# Sheet1.net
KiCad netlist of a schematic drawn in Altium Designer
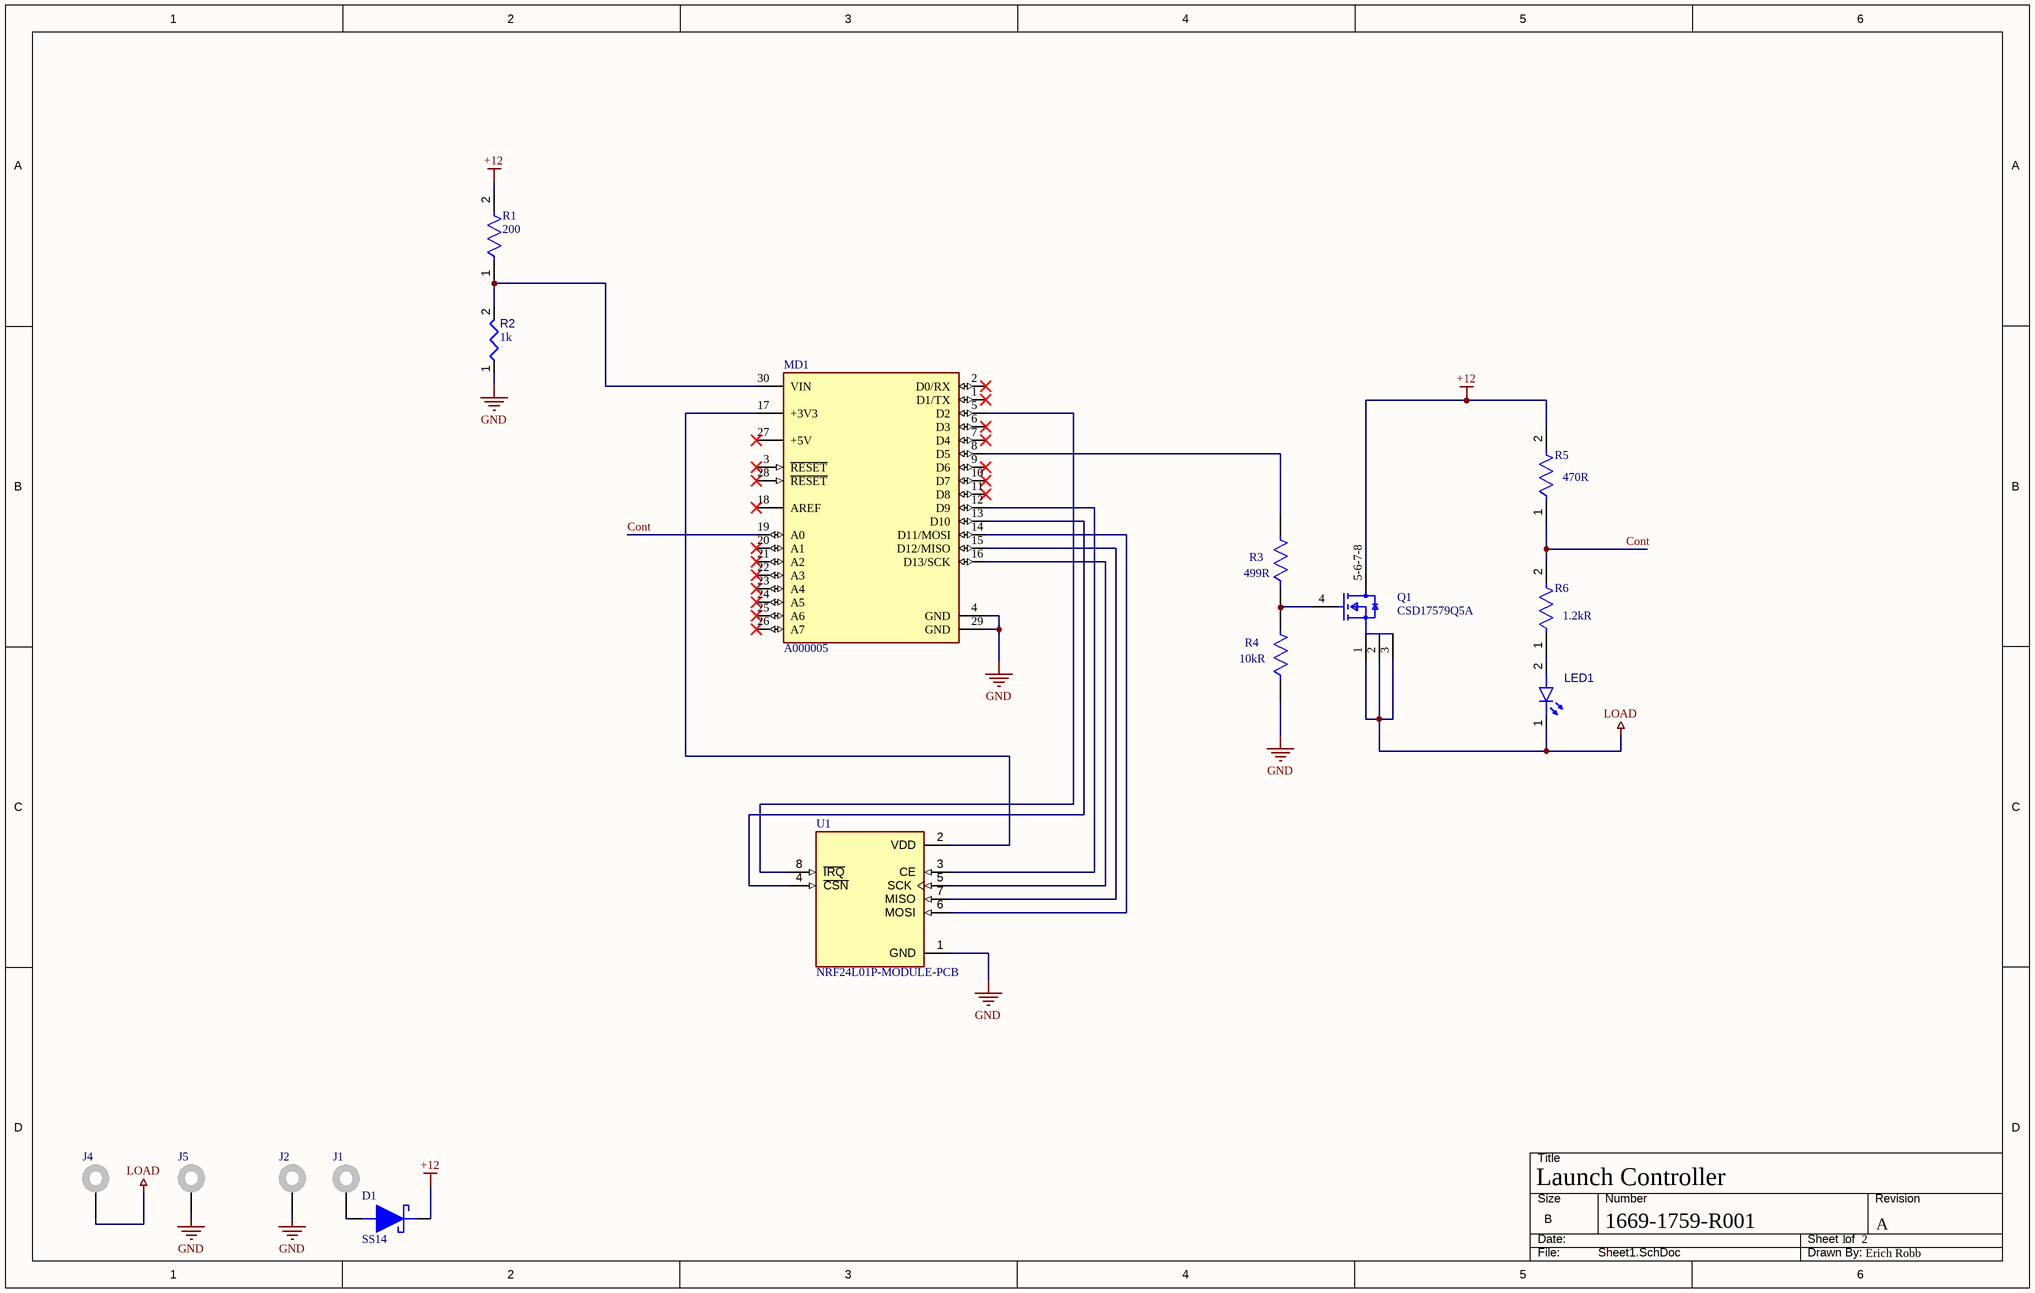
[diagram p0: Sheet1.SchDoc]

(export (version "E")
  (design (tool "Eeschema 10.0.6"))
  (components
    (comp (ref "D1")
      (value "SS14")
      (footprint "DIOM5227X270N")
      (description "Diode Schottky 40 V 1A Surface Mount DO-214AC (SMA)")
      (fields (field (name "MF") "ON Semiconductor"))
      (libsource (lib "Erich Robb") (part "SS14"))
    )
    (comp (ref "J1")
      (value "575-8")
      (footprint "KSTN-575-8")
      (description "Non-Insulated Jack, Through Hole, RoHS, Bulk")
      (fields (field (name "MANUFACTURER") "Keystone"))
      (libsource (lib "Altium Content Vault") (part "KSTN-575-8"))
    )
    (comp (ref "J2")
      (value "575-8")
      (footprint "KSTN-575-8")
      (description "Non-Insulated Jack, Through Hole, RoHS, Bulk")
      (fields (field (name "MANUFACTURER") "Keystone"))
      (libsource (lib "Altium Content Vault") (part "KSTN-575-8"))
    )
    (comp (ref "J4")
      (value "575-8")
      (footprint "KSTN-575-8")
      (description "Non-Insulated Jack, Through Hole, RoHS, Bulk")
      (fields (field (name "MANUFACTURER") "Keystone"))
      (libsource (lib "Altium Content Vault") (part "KSTN-575-8"))
    )
    (comp (ref "J5")
      (value "575-8")
      (footprint "KSTN-575-8")
      (description "Non-Insulated Jack, Through Hole, RoHS, Bulk")
      (fields (field (name "MANUFACTURER") "Keystone"))
      (libsource (lib "Altium Content Vault") (part "KSTN-575-8"))
    )
    (comp (ref "LED1")
      (value "QBLP595-IB")
      (footprint "QTB-QBLP595_V")
      (description "Chip LED 0402, Blue, 0.02 A, 3.1 to 3.7 V, -40 to 80 degC, 2-Pin SMD, RoHS, Tape and Reel")
      (libsource (lib "Erich Robb") (part "LED-KA-2"))
    )
    (comp (ref "MD1")
      (value "A000005")
      (footprint "FP-A000005-MFG")
      (description "ARDUINO NANO ATMEGA328 EVAL BRD")
      (libsource (lib "Altium Content Vault") (part "d190c066e99afd1c6882cf92e11b2cc"))
    )
    (comp (ref "Q1")
      (value "CSD17579Q5A")
      (footprint "FP-DQJ0008A-MFG")
      (description "30V, N ch NexFET MOSFET, single SON5x6, 13.3mOhm 8-VSONP")
      (fields (field (name "MF") "Texas Instruments"))
      (libsource (lib "Erich Robb") (part "95ca5d46c4c8fe7d84c4fb5e2abfe3c"))
    )
    (comp (ref "R1")
      (value "200")
      (footprint "FP-RC3216-IPC_A")
      (fields
        (field (name "POWER") "250mW")
        (field (name "TOLERANCE") "1%")
        (field (name "Comment") "RC3216F201CS")
      )
      (libsource (lib "Erich Robb") (part "1029c3af85768c4190bb7ad29bc67b5"))
    )
    (comp (ref "R2")
      (value "1k")
      (footprint "FP-MCA1206-IPC_A")
      (description "Fixed Resistor, Thin Film, 0.25W, 1000ohm, 200V, 1% +/-Tol, 50ppm/Cel, Surface Mount, 1206")
      (fields (field (name "POWER") "250mW") (field (name "TOLERANCE") "1%"))
      (libsource (lib "Erich Robb") (part "RES-2"))
    )
    (comp (ref "R3")
      (value "499R")
      (footprint "FP-RT1206-MFG")
      (description "RES SMD 499 OHM 1% 1/4W 1206")
      (fields
        (field (name "MANUFACTURER PART NUMBER") "RT1206FRE07499RL")
        (field (name "TOLERANCE") "0.0002")
      )
      (libsource (lib "") (part "1029c3af85768c4190bb7ad29bc67b5_1"))
    )
    (comp (ref "R4")
      (value "CRCW120610K0FKEA")
      (footprint "FP-CRCW1206-e3-IPC_C")
      (description "RES Thick Film, 10kΩ, 1%, 0.25W, 100ppm/°C, 1206")
      (fields (field (name "TOLERANCE") "1%") (field (name "RESISTANCE") "10kR"))
      (libsource (lib "") (part "1029c3af85768c4190bb7ad29bc67b5_1"))
    )
    (comp (ref "R5")
      (value "CRCW1206470RJNEA")
      (footprint "FP-CRCW1206-e3-IPC_A")
      (description "RES Thick Film, 470Ω, 5%, 0.25W, 200ppm/°C, 1206")
      (fields (field (name "TOLERANCE") "5%") (field (name "RESISTANCE") "470R"))
      (libsource (lib "Altium Content Vault") (part "1029c3af85768c4190bb7ad29bc67b5"))
    )
    (comp (ref "R6")
      (value "RC3216J122CS")
      (footprint "FP-RC3216-IPC_A")
      (description "Res Thick Film 1206 1.2kΩ 5% 0.25W ±100ppm/°C Molded SMD T/R")
      (fields (field (name "TOLERANCE") "5%") (field (name "RESISTANCE") "1.2kR"))
      (libsource (lib "Altium Content Vault") (part "1029c3af85768c4190bb7ad29bc67b5"))
    )
    (comp (ref "U1")
      (value "NRF24L01P-MODULE-PCB")
      (footprint "XCVR_NRF24L01P-MODULE-PCB")
      (description "- Transceiver For Use With nRF24L01+")
      (fields (field (name "MF") "Nordic Semiconductor"))
      (libsource (lib "Erich Robb") (part "NRF24L01P-MODULE-PCB"))
    )
  )
  (nets
    (net (code "1") (name "+12") (class "Default")
      (node (ref "D1") (pin "1") (pinfunction "K_1") (pintype "passive"))
      (node (ref "Q1") (pin "5-6-7-8") (pinfunction "D_5-6-7-8") (pintype "passive"))
      (node (ref "R1") (pin "2") (pinfunction "2_2") (pintype "passive"))
      (node (ref "R5") (pin "2") (pinfunction "2_2") (pintype "passive"))
    )
    (net (code "2") (name "/Cont") (class "Default")
      (node (ref "MD1") (pin "19") (pinfunction "A0_19") (pintype "bidirectional"))
      (node (ref "R5") (pin "1") (pinfunction "1_1") (pintype "passive"))
      (node (ref "R6") (pin "2") (pinfunction "2_2") (pintype "passive"))
    )
    (net (code "3") (name "GND") (class "Default")
      (node (ref "J2") (pin "1") (pinfunction "1_1") (pintype "passive"))
      (node (ref "J5") (pin "1") (pinfunction "1_1") (pintype "passive"))
      (node (ref "MD1") (pin "29") (pinfunction "GND_29") (pintype "power_in"))
      (node (ref "MD1") (pin "4") (pinfunction "GND_4") (pintype "power_in"))
      (node (ref "R2") (pin "1") (pinfunction "1_1") (pintype "passive"))
      (node (ref "R4") (pin "1") (pinfunction "1_1") (pintype "passive"))
      (node (ref "U1") (pin "1") (pinfunction "GND_1") (pintype "power_in"))
    )
    (net (code "4") (name "LOAD") (class "Default")
      (node (ref "J4") (pin "1") (pinfunction "1_1") (pintype "passive"))
      (node (ref "LED1") (pin "1") (pinfunction "K_1") (pintype "passive"))
      (node (ref "Q1") (pin "1") (pinfunction "S_1") (pintype "passive"))
      (node (ref "Q1") (pin "2") (pinfunction "S_2") (pintype "passive"))
      (node (ref "Q1") (pin "3") (pinfunction "S_3") (pintype "passive"))
    )
    (net (code "5") (name "Net-(D1-A)") (class "Default")
      (node (ref "D1") (pin "2") (pinfunction "A_2") (pintype "passive"))
      (node (ref "J1") (pin "1") (pinfunction "1_1") (pintype "passive"))
    )
    (net (code "6") (name "Net-(LED1-A)") (class "Default")
      (node (ref "LED1") (pin "2") (pinfunction "A_2") (pintype "passive"))
      (node (ref "R6") (pin "1") (pinfunction "1_1") (pintype "passive"))
    )
    (net (code "7") (name "Net-(MD1-+3V3)") (class "Default")
      (node (ref "MD1") (pin "17") (pinfunction "+3V3_17") (pintype "power_in"))
      (node (ref "U1") (pin "2") (pinfunction "VDD_2") (pintype "power_in"))
    )
    (net (code "8") (name "Net-(MD1-D2)") (class "Default")
      (node (ref "MD1") (pin "5") (pinfunction "D2_5") (pintype "bidirectional"))
      (node (ref "U1") (pin "8") (pinfunction "~{IRQ}_8") (pintype "input"))
    )
    (net (code "9") (name "Net-(MD1-D5)") (class "Default")
      (node (ref "MD1") (pin "8") (pinfunction "D5_8") (pintype "bidirectional"))
      (node (ref "R3") (pin "2") (pinfunction "2_2") (pintype "passive"))
    )
    (net (code "10") (name "Net-(MD1-D9)") (class "Default")
      (node (ref "MD1") (pin "12") (pinfunction "D9_12") (pintype "bidirectional"))
      (node (ref "U1") (pin "3") (pinfunction "CE_3") (pintype "input"))
    )
    (net (code "11") (name "Net-(MD1-D10)") (class "Default")
      (node (ref "MD1") (pin "13") (pinfunction "D10_13") (pintype "bidirectional"))
      (node (ref "U1") (pin "4") (pinfunction "~{CSN}_4") (pintype "input"))
    )
    (net (code "12") (name "Net-(MD1-D11{slash}MOSI)") (class "Default")
      (node (ref "MD1") (pin "14") (pinfunction "D11/MOSI_14") (pintype "bidirectional"))
      (node (ref "U1") (pin "6") (pinfunction "MOSI_6") (pintype "input"))
    )
    (net (code "13") (name "Net-(MD1-D12{slash}MISO)") (class "Default")
      (node (ref "MD1") (pin "15") (pinfunction "D12/MISO_15") (pintype "bidirectional"))
      (node (ref "U1") (pin "7") (pinfunction "MISO_7") (pintype "input"))
    )
    (net (code "14") (name "Net-(MD1-D13{slash}SCK)") (class "Default")
      (node (ref "MD1") (pin "16") (pinfunction "D13/SCK_16") (pintype "bidirectional"))
      (node (ref "U1") (pin "5") (pinfunction "SCK_5") (pintype "input"))
    )
    (net (code "15") (name "Net-(MD1-VIN)") (class "Default")
      (node (ref "MD1") (pin "30") (pinfunction "VIN_30") (pintype "power_in"))
      (node (ref "R1") (pin "1") (pinfunction "1_1") (pintype "passive"))
      (node (ref "R2") (pin "2") (pinfunction "2_2") (pintype "passive"))
    )
    (net (code "16") (name "Net-(Q1-G)") (class "Default")
      (node (ref "Q1") (pin "4") (pinfunction "G_4") (pintype "passive"))
      (node (ref "R3") (pin "1") (pinfunction "1_1") (pintype "passive"))
      (node (ref "R4") (pin "2") (pinfunction "2_2") (pintype "passive"))
    )
    (net (code "17") (name "unconnected-(MD1-+5V-Pad27)") (class "Default")
      (node (ref "MD1") (pin "27") (pinfunction "+5V_27") (pintype "power_in+no_connect"))
    )
    (net (code "18") (name "unconnected-(MD1-A1-Pad20)") (class "Default")
      (node (ref "MD1") (pin "20") (pinfunction "A1_20") (pintype "bidirectional+no_connect"))
    )
    (net (code "19") (name "unconnected-(MD1-A2-Pad21)") (class "Default")
      (node (ref "MD1") (pin "21") (pinfunction "A2_21") (pintype "bidirectional+no_connect"))
    )
    (net (code "20") (name "unconnected-(MD1-A3-Pad22)") (class "Default")
      (node (ref "MD1") (pin "22") (pinfunction "A3_22") (pintype "bidirectional+no_connect"))
    )
    (net (code "21") (name "unconnected-(MD1-A4-Pad23)") (class "Default")
      (node (ref "MD1") (pin "23") (pinfunction "A4_23") (pintype "bidirectional+no_connect"))
    )
    (net (code "22") (name "unconnected-(MD1-A5-Pad24)") (class "Default")
      (node (ref "MD1") (pin "24") (pinfunction "A5_24") (pintype "bidirectional+no_connect"))
    )
    (net (code "23") (name "unconnected-(MD1-A6-Pad25)") (class "Default")
      (node (ref "MD1") (pin "25") (pinfunction "A6_25") (pintype "bidirectional+no_connect"))
    )
    (net (code "24") (name "unconnected-(MD1-A7-Pad26)") (class "Default")
      (node (ref "MD1") (pin "26") (pinfunction "A7_26") (pintype "bidirectional+no_connect"))
    )
    (net (code "25") (name "unconnected-(MD1-AREF-Pad18)") (class "Default")
      (node (ref "MD1") (pin "18") (pinfunction "AREF_18") (pintype "passive+no_connect"))
    )
    (net (code "26") (name "unconnected-(MD1-D0{slash}RX-Pad2)") (class "Default")
      (node (ref "MD1") (pin "2") (pinfunction "D0/RX_2") (pintype "bidirectional+no_connect"))
    )
    (net (code "27") (name "unconnected-(MD1-D1{slash}TX-Pad1)") (class "Default")
      (node (ref "MD1") (pin "1") (pinfunction "D1/TX_1") (pintype "bidirectional+no_connect"))
    )
    (net (code "28") (name "unconnected-(MD1-D3-Pad6)") (class "Default")
      (node (ref "MD1") (pin "6") (pinfunction "D3_6") (pintype "bidirectional+no_connect"))
    )
    (net (code "29") (name "unconnected-(MD1-D4-Pad7)") (class "Default")
      (node (ref "MD1") (pin "7") (pinfunction "D4_7") (pintype "bidirectional+no_connect"))
    )
    (net (code "30") (name "unconnected-(MD1-D6-Pad9)") (class "Default")
      (node (ref "MD1") (pin "9") (pinfunction "D6_9") (pintype "bidirectional+no_connect"))
    )
    (net (code "31") (name "unconnected-(MD1-D7-Pad10)") (class "Default")
      (node (ref "MD1") (pin "10") (pinfunction "D7_10") (pintype "bidirectional+no_connect"))
    )
    (net (code "32") (name "unconnected-(MD1-D8-Pad11)") (class "Default")
      (node (ref "MD1") (pin "11") (pinfunction "D8_11") (pintype "bidirectional+no_connect"))
    )
    (net (code "33") (name "unconnected-(MD1-~{RESET}-Pad3)") (class "Default")
      (node (ref "MD1") (pin "3") (pinfunction "~{RESET}_3") (pintype "input+no_connect"))
    )
    (net (code "34") (name "unconnected-(MD1-~{RESET}-Pad28)") (class "Default")
      (node (ref "MD1") (pin "28") (pinfunction "~{RESET}_28") (pintype "input+no_connect"))
    )
  )
)
